# USB2514_POWER_DISTRIBUTION_SWITCHES.net
KiCad netlist of a schematic drawn in Altium Designer
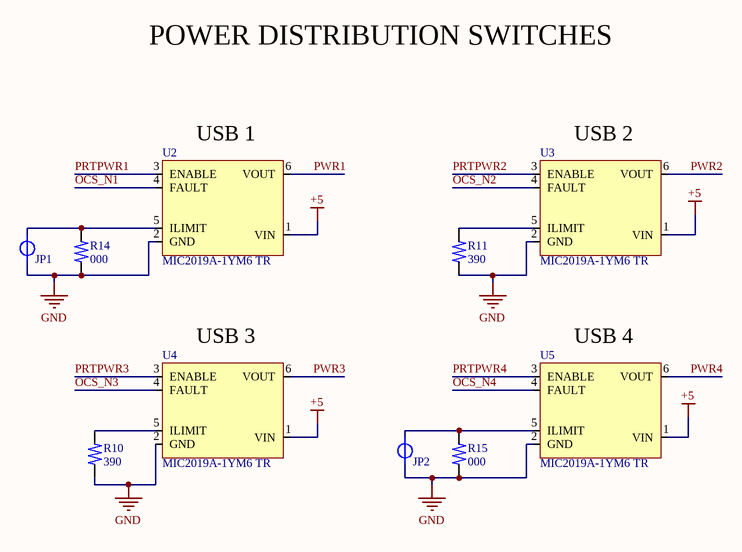
[diagram p0: USB2514 POWER DISTRIBUTION SWITCHES.SchDoc]

(export (version "E")
  (design (tool "Eeschema 10.0.6"))
  (components
    (comp (ref "JP1")
      (value "JUMP_N-C")
      (footprint "JUMP_N-C 0,254")
      (libsource (lib "SCH_LIB") (part "JUMP_N-C"))
    )
    (comp (ref "JP2")
      (value "JUMP_N-C")
      (footprint "JUMP_N-C 0,254")
      (libsource (lib "SCH_LIB") (part "JUMP_N-C"))
    )
    (comp (ref "R10")
      (value "390")
      (footprint "RESC1608X06N-0603")
      (libsource (lib "SCH_LIB") (part "RES_0603_1K"))
    )
    (comp (ref "R11")
      (value "390")
      (footprint "RESC1608X06N-0603")
      (libsource (lib "SCH_LIB") (part "RES_0603_1K"))
    )
    (comp (ref "R14")
      (value "000")
      (footprint "RESC1608X06N-0603")
      (libsource (lib "SCH_LIB") (part "RES_0603_1K"))
    )
    (comp (ref "R15")
      (value "000")
      (footprint "RESC1608X06N-0603")
      (libsource (lib "SCH_LIB") (part "RES_0603_1K"))
    )
    (comp (ref "U2")
      (value "MIC2019A-1YM6 TR")
      (footprint "SOT95P280X90-6N")
      (libsource (lib "SCH_LIB") (part "MIC2019A-1YM6 TR"))
    )
    (comp (ref "U3")
      (value "MIC2019A-1YM6 TR")
      (footprint "SOT95P280X90-6N")
      (libsource (lib "SCH_LIB") (part "MIC2019A-1YM6 TR"))
    )
    (comp (ref "U4")
      (value "MIC2019A-1YM6 TR")
      (footprint "SOT95P280X90-6N")
      (libsource (lib "SCH_LIB") (part "MIC2019A-1YM6 TR"))
    )
    (comp (ref "U5")
      (value "MIC2019A-1YM6 TR")
      (footprint "SOT95P280X90-6N")
      (libsource (lib "SCH_LIB") (part "MIC2019A-1YM6 TR"))
    )
  )
  (nets
    (net (code "1") (name "+5") (class "Default")
      (node (ref "U2") (pin "1") (pinfunction "VIN_1") (pintype "passive"))
      (node (ref "U3") (pin "1") (pinfunction "VIN_1") (pintype "passive"))
      (node (ref "U4") (pin "1") (pinfunction "VIN_1") (pintype "passive"))
      (node (ref "U5") (pin "1") (pinfunction "VIN_1") (pintype "passive"))
    )
    (net (code "2") (name "/OCS_N1") (class "Default")
      (node (ref "U2") (pin "4") (pinfunction "FAULT_4") (pintype "passive"))
    )
    (net (code "3") (name "/OCS_N2") (class "Default")
      (node (ref "U3") (pin "4") (pinfunction "FAULT_4") (pintype "passive"))
    )
    (net (code "4") (name "/OCS_N3") (class "Default")
      (node (ref "U4") (pin "4") (pinfunction "FAULT_4") (pintype "passive"))
    )
    (net (code "5") (name "/OCS_N4") (class "Default")
      (node (ref "U5") (pin "4") (pinfunction "FAULT_4") (pintype "passive"))
    )
    (net (code "6") (name "/PRTPWR1") (class "Default")
      (node (ref "U2") (pin "3") (pinfunction "ENABLE_3") (pintype "passive"))
    )
    (net (code "7") (name "/PRTPWR2") (class "Default")
      (node (ref "U3") (pin "3") (pinfunction "ENABLE_3") (pintype "passive"))
    )
    (net (code "8") (name "/PRTPWR3") (class "Default")
      (node (ref "U4") (pin "3") (pinfunction "ENABLE_3") (pintype "passive"))
    )
    (net (code "9") (name "/PRTPWR4") (class "Default")
      (node (ref "U5") (pin "3") (pinfunction "ENABLE_3") (pintype "passive"))
    )
    (net (code "10") (name "/PWR1") (class "Default")
      (node (ref "U2") (pin "6") (pinfunction "VOUT_6") (pintype "passive"))
    )
    (net (code "11") (name "/PWR2") (class "Default")
      (node (ref "U3") (pin "6") (pinfunction "VOUT_6") (pintype "passive"))
    )
    (net (code "12") (name "/PWR3") (class "Default")
      (node (ref "U4") (pin "6") (pinfunction "VOUT_6") (pintype "passive"))
    )
    (net (code "13") (name "/PWR4") (class "Default")
      (node (ref "U5") (pin "6") (pinfunction "VOUT_6") (pintype "passive"))
    )
    (net (code "14") (name "GND") (class "Default")
      (node (ref "JP1") (pin "1") (pinfunction "1_1") (pintype "passive"))
      (node (ref "JP2") (pin "1") (pinfunction "1_1") (pintype "passive"))
      (node (ref "R10") (pin "1") (pinfunction "1_1") (pintype "passive"))
      (node (ref "R11") (pin "1") (pinfunction "1_1") (pintype "passive"))
      (node (ref "R14") (pin "1") (pinfunction "1_1") (pintype "passive"))
      (node (ref "R15") (pin "1") (pinfunction "1_1") (pintype "passive"))
      (node (ref "U2") (pin "2") (pinfunction "GND_2") (pintype "passive"))
      (node (ref "U3") (pin "2") (pinfunction "GND_2") (pintype "passive"))
      (node (ref "U4") (pin "2") (pinfunction "GND_2") (pintype "passive"))
      (node (ref "U5") (pin "2") (pinfunction "GND_2") (pintype "passive"))
    )
    (net (code "15") (name "Net-(U2-ILIMIT)") (class "Default")
      (node (ref "JP1") (pin "2") (pinfunction "2_2") (pintype "passive"))
      (node (ref "R14") (pin "2") (pinfunction "2_2") (pintype "passive"))
      (node (ref "U2") (pin "5") (pinfunction "ILIMIT_5") (pintype "passive"))
    )
    (net (code "16") (name "Net-(U3-ILIMIT)") (class "Default")
      (node (ref "R11") (pin "2") (pinfunction "2_2") (pintype "passive"))
      (node (ref "U3") (pin "5") (pinfunction "ILIMIT_5") (pintype "passive"))
    )
    (net (code "17") (name "Net-(U4-ILIMIT)") (class "Default")
      (node (ref "R10") (pin "2") (pinfunction "2_2") (pintype "passive"))
      (node (ref "U4") (pin "5") (pinfunction "ILIMIT_5") (pintype "passive"))
    )
    (net (code "18") (name "Net-(U5-ILIMIT)") (class "Default")
      (node (ref "JP2") (pin "2") (pinfunction "2_2") (pintype "passive"))
      (node (ref "R15") (pin "2") (pinfunction "2_2") (pintype "passive"))
      (node (ref "U5") (pin "5") (pinfunction "ILIMIT_5") (pintype "passive"))
    )
  )
)
